# Board.net
KiCad netlist of a schematic drawn in EAGLE
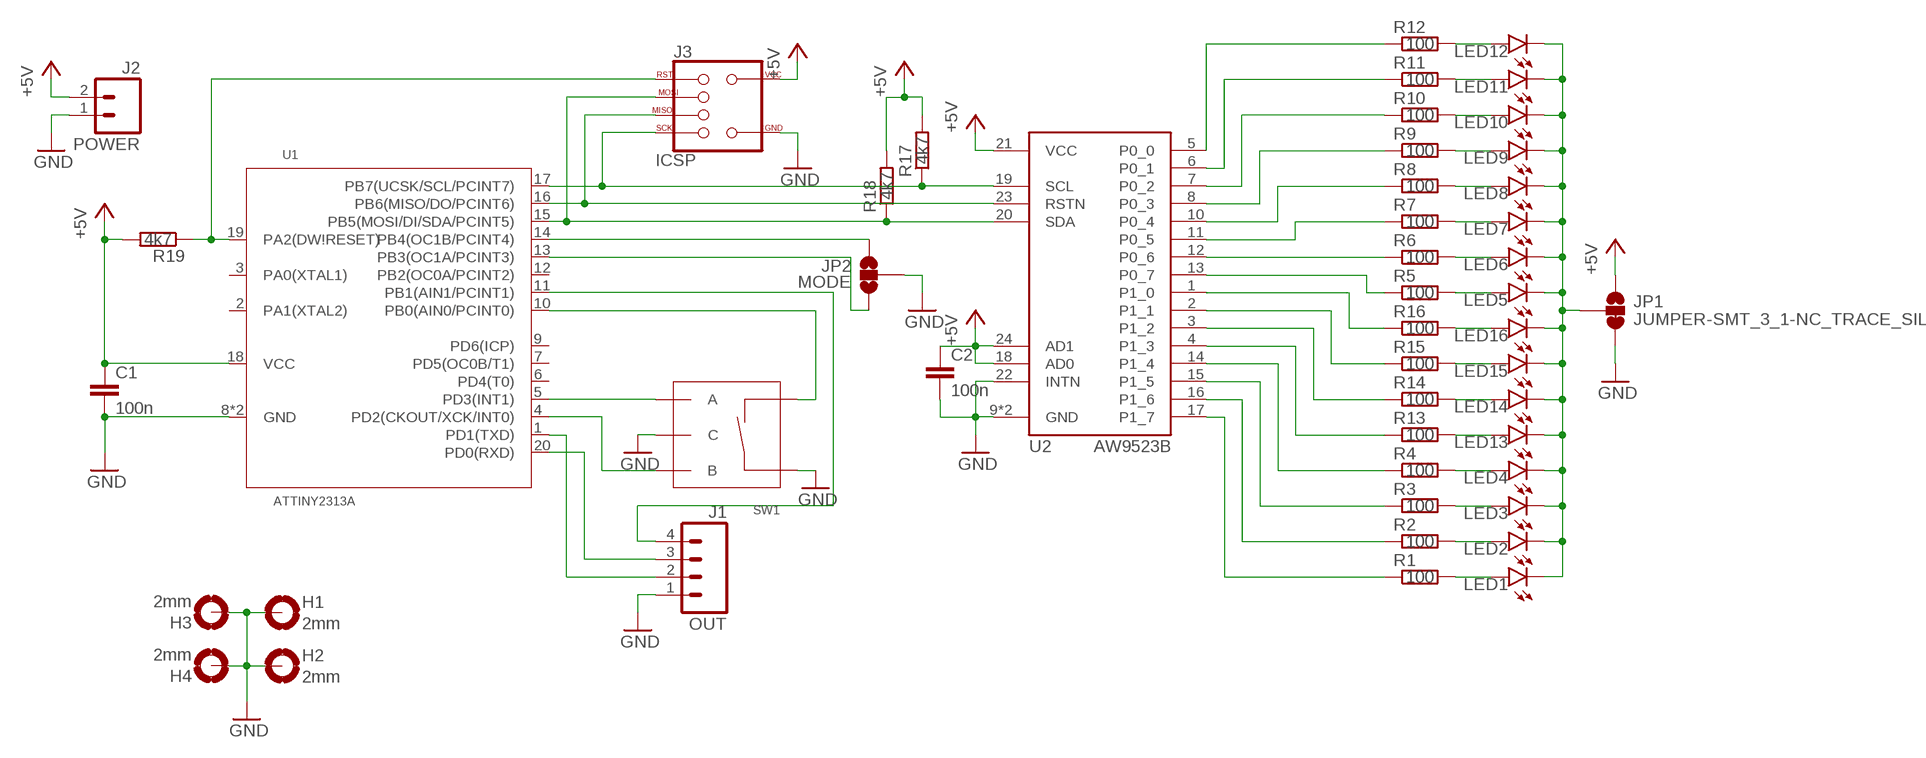
[diagram p0: schematic, sheet 1]

(export (version "E")
  (design (tool "Eeschema 10.0.6"))
  (components
    (comp (ref "C1")
      (value "100n")
      (footprint "eagle-import:C0402")
      (libsource (lib "eagle-import") (part "C-EUC0402"))
    )
    (comp (ref "C2")
      (value "100n")
      (footprint "eagle-import:C0402")
      (libsource (lib "eagle-import") (part "C-EUC0402"))
    )
    (comp (ref "H1")
      (value "2mm")
      (footprint "eagle-import:2,0-PAD")
      (libsource (lib "eagle-import") (part "MOUNT-PAD2MM"))
    )
    (comp (ref "H2")
      (value "2mm")
      (footprint "eagle-import:2,0-PAD")
      (libsource (lib "eagle-import") (part "MOUNT-PAD2MM"))
    )
    (comp (ref "H3")
      (value "2mm")
      (footprint "eagle-import:2,0-PAD")
      (libsource (lib "eagle-import") (part "MOUNT-PAD2MM"))
    )
    (comp (ref "H4")
      (value "2mm")
      (footprint "eagle-import:2,0-PAD")
      (libsource (lib "eagle-import") (part "MOUNT-PAD2MM"))
    )
    (comp (ref "J1")
      (value "OUT")
      (footprint "eagle-import:JST-4-PTH-VERT")
      (libsource (lib "eagle-import") (part "JST-XH4"))
    )
    (comp (ref "J2")
      (value "POWER")
      (footprint "eagle-import:JST-2-PTH-VERT")
      (libsource (lib "eagle-import") (part "JST-XH2"))
    )
    (comp (ref "J3")
      (value "ICSP")
      (footprint "eagle-import:MINI-ISP-LABELS")
      (libsource (lib "eagle-import") (part "MINI-ISP-LABELS"))
    )
    (comp (ref "JP1")
      (value "JUMPER-SMT_3_1-NC_TRACE_SILK")
      (footprint "eagle-import:SMT-JUMPER_3_1-NC_TRACE_SILK")
      (libsource (lib "eagle-import") (part "JUMPER-SMT_3_1-NC_TRACE_SILK"))
    )
    (comp (ref "JP2")
      (value "MODE")
      (footprint "eagle-import:SMT-JUMPER_3_NO_SILK")
      (libsource (lib "eagle-import") (part "JUMPER-SMT_3_NO_SILK"))
    )
    (comp (ref "LED1")
      (value "LED-BLUE0603")
      (footprint "eagle-import:0603-BLUE")
      (libsource (lib "eagle-import") (part "LED-BLUE0603"))
    )
    (comp (ref "LED2")
      (value "LED-BLUE0603")
      (footprint "eagle-import:0603-BLUE")
      (libsource (lib "eagle-import") (part "LED-BLUE0603"))
    )
    (comp (ref "LED3")
      (value "LED-BLUE0603")
      (footprint "eagle-import:0603-BLUE")
      (libsource (lib "eagle-import") (part "LED-BLUE0603"))
    )
    (comp (ref "LED4")
      (value "LED-BLUE0603")
      (footprint "eagle-import:0603-BLUE")
      (libsource (lib "eagle-import") (part "LED-BLUE0603"))
    )
    (comp (ref "LED5")
      (value "LED-BLUE0603")
      (footprint "eagle-import:0603-BLUE")
      (libsource (lib "eagle-import") (part "LED-BLUE0603"))
    )
    (comp (ref "LED6")
      (value "LED-BLUE0603")
      (footprint "eagle-import:0603-BLUE")
      (libsource (lib "eagle-import") (part "LED-BLUE0603"))
    )
    (comp (ref "LED7")
      (value "LED-BLUE0603")
      (footprint "eagle-import:0603-BLUE")
      (libsource (lib "eagle-import") (part "LED-BLUE0603"))
    )
    (comp (ref "LED8")
      (value "LED-BLUE0603")
      (footprint "eagle-import:0603-BLUE")
      (libsource (lib "eagle-import") (part "LED-BLUE0603"))
    )
    (comp (ref "LED9")
      (value "LED-BLUE0603")
      (footprint "eagle-import:0603-BLUE")
      (libsource (lib "eagle-import") (part "LED-BLUE0603"))
    )
    (comp (ref "LED10")
      (value "LED-BLUE0603")
      (footprint "eagle-import:0603-BLUE")
      (libsource (lib "eagle-import") (part "LED-BLUE0603"))
    )
    (comp (ref "LED11")
      (value "LED-BLUE0603")
      (footprint "eagle-import:0603-BLUE")
      (libsource (lib "eagle-import") (part "LED-BLUE0603"))
    )
    (comp (ref "LED12")
      (value "LED-BLUE0603")
      (footprint "eagle-import:0603-BLUE")
      (libsource (lib "eagle-import") (part "LED-BLUE0603"))
    )
    (comp (ref "LED13")
      (value "LED-BLUE0603")
      (footprint "eagle-import:0603-BLUE")
      (libsource (lib "eagle-import") (part "LED-BLUE0603"))
    )
    (comp (ref "LED14")
      (value "LED-BLUE0603")
      (footprint "eagle-import:0603-BLUE")
      (libsource (lib "eagle-import") (part "LED-BLUE0603"))
    )
    (comp (ref "LED15")
      (value "LED-BLUE0603")
      (footprint "eagle-import:0603-BLUE")
      (libsource (lib "eagle-import") (part "LED-BLUE0603"))
    )
    (comp (ref "LED16")
      (value "LED-BLUE0603")
      (footprint "eagle-import:0603-BLUE")
      (libsource (lib "eagle-import") (part "LED-BLUE0603"))
    )
    (comp (ref "R1")
      (value "100")
      (footprint "eagle-import:R0402")
      (libsource (lib "eagle-import") (part "R-EU_R0402"))
    )
    (comp (ref "R2")
      (value "100")
      (footprint "eagle-import:R0402")
      (libsource (lib "eagle-import") (part "R-EU_R0402"))
    )
    (comp (ref "R3")
      (value "100")
      (footprint "eagle-import:R0402")
      (libsource (lib "eagle-import") (part "R-EU_R0402"))
    )
    (comp (ref "R4")
      (value "100")
      (footprint "eagle-import:R0402")
      (libsource (lib "eagle-import") (part "R-EU_R0402"))
    )
    (comp (ref "R5")
      (value "100")
      (footprint "eagle-import:R0402")
      (libsource (lib "eagle-import") (part "R-EU_R0402"))
    )
    (comp (ref "R6")
      (value "100")
      (footprint "eagle-import:R0402")
      (libsource (lib "eagle-import") (part "R-EU_R0402"))
    )
    (comp (ref "R7")
      (value "100")
      (footprint "eagle-import:R0402")
      (libsource (lib "eagle-import") (part "R-EU_R0402"))
    )
    (comp (ref "R8")
      (value "100")
      (footprint "eagle-import:R0402")
      (libsource (lib "eagle-import") (part "R-EU_R0402"))
    )
    (comp (ref "R9")
      (value "100")
      (footprint "eagle-import:R0402")
      (libsource (lib "eagle-import") (part "R-EU_R0402"))
    )
    (comp (ref "R10")
      (value "100")
      (footprint "eagle-import:R0402")
      (libsource (lib "eagle-import") (part "R-EU_R0402"))
    )
    (comp (ref "R11")
      (value "100")
      (footprint "eagle-import:R0402")
      (libsource (lib "eagle-import") (part "R-EU_R0402"))
    )
    (comp (ref "R12")
      (value "100")
      (footprint "eagle-import:R0402")
      (libsource (lib "eagle-import") (part "R-EU_R0402"))
    )
    (comp (ref "R13")
      (value "100")
      (footprint "eagle-import:R0402")
      (libsource (lib "eagle-import") (part "R-EU_R0402"))
    )
    (comp (ref "R14")
      (value "100")
      (footprint "eagle-import:R0402")
      (libsource (lib "eagle-import") (part "R-EU_R0402"))
    )
    (comp (ref "R15")
      (value "100")
      (footprint "eagle-import:R0402")
      (libsource (lib "eagle-import") (part "R-EU_R0402"))
    )
    (comp (ref "R16")
      (value "100")
      (footprint "eagle-import:R0402")
      (libsource (lib "eagle-import") (part "R-EU_R0402"))
    )
    (comp (ref "R17")
      (value "4k7")
      (footprint "eagle-import:R0402")
      (libsource (lib "eagle-import") (part "R-EU_R0402"))
    )
    (comp (ref "R18")
      (value "4k7")
      (footprint "eagle-import:R0402")
      (libsource (lib "eagle-import") (part "R-EU_R0402"))
    )
    (comp (ref "R19")
      (value "4k7")
      (footprint "eagle-import:R0402")
      (libsource (lib "eagle-import") (part "R-EU_R0402"))
    )
    (comp (ref "SW1")
      (value "ROTARTY_ENCODER")
      (footprint "eagle-import:ROTARY_ENC_PLAIN")
      (libsource (lib "eagle-import") (part "ROTARTY_ENCODER"))
    )
    (comp (ref "U1")
      (value "ATTINY2313A")
      (footprint "eagle-import:QFN50P400X400X80-21T260N")
      (libsource (lib "eagle-import") (part "ATTINY2313A"))
    )
    (comp (ref "U2")
      (value "AW9523B")
      (footprint "eagle-import:QFN50P400X400X80-25T270N")
      (libsource (lib "eagle-import") (part "AW9523B"))
    )
  )
  (nets
    (net (code "1") (name "+5V") (class "Default")
      (node (ref "C1") (pin "1") (pinfunction "1_1") (pintype "passive"))
      (node (ref "C2") (pin "1") (pinfunction "1_1") (pintype "passive"))
      (node (ref "J2") (pin "2") (pinfunction "2_2") (pintype "passive"))
      (node (ref "J3") (pin "VDD") (pinfunction "2_VDD") (pintype "passive"))
      (node (ref "JP1") (pin "1") (pinfunction "1_1") (pintype "passive"))
      (node (ref "R17") (pin "2") (pinfunction "2_2") (pintype "passive"))
      (node (ref "R18") (pin "2") (pinfunction "2_2") (pintype "passive"))
      (node (ref "R19") (pin "2") (pinfunction "2_2") (pintype "passive"))
      (node (ref "U1") (pin "18") (pinfunction "VCC_18") (pintype "power_in"))
      (node (ref "U2") (pin "18") (pinfunction "AD0_18") (pintype "input"))
      (node (ref "U2") (pin "21") (pinfunction "VCC_21") (pintype "power_in"))
      (node (ref "U2") (pin "24") (pinfunction "AD1_24") (pintype "input"))
    )
    (net (code "2") (name "GND") (class "Default")
      (node (ref "C1") (pin "2") (pinfunction "2_2") (pintype "passive"))
      (node (ref "C2") (pin "2") (pinfunction "2_2") (pintype "passive"))
      (node (ref "H1") (pin "B2,0") (pinfunction "MOUNT_B2,0") (pintype "passive"))
      (node (ref "H2") (pin "B2,0") (pinfunction "MOUNT_B2,0") (pintype "passive"))
      (node (ref "H3") (pin "B2,0") (pinfunction "MOUNT_B2,0") (pintype "passive"))
      (node (ref "H4") (pin "B2,0") (pinfunction "MOUNT_B2,0") (pintype "passive"))
      (node (ref "J1") (pin "1") (pinfunction "1_1") (pintype "passive"))
      (node (ref "J2") (pin "1") (pinfunction "1_1") (pintype "passive"))
      (node (ref "J3") (pin "GND") (pinfunction "6_GND") (pintype "passive"))
      (node (ref "JP1") (pin "3") (pinfunction "3_3") (pintype "passive"))
      (node (ref "JP2") (pin "2") (pinfunction "2_2") (pintype "passive"))
      (node (ref "SW1") (pin "C") (pinfunction "C_C") (pintype "bidirectional"))
      (node (ref "SW1") (pin "SW+") (pinfunction "SW+_SW+") (pintype "bidirectional"))
      (node (ref "U1") (pin "21") (pinfunction "GND_21") (pintype "input"))
      (node (ref "U1") (pin "8") (pinfunction "GND_8") (pintype "input"))
      (node (ref "U2") (pin "22") (pinfunction "INTN_22") (pintype "output"))
      (node (ref "U2") (pin "25") (pinfunction "GND_25") (pintype "power_in"))
      (node (ref "U2") (pin "9") (pinfunction "GND_9") (pintype "power_in"))
    )
    (net (code "3") (name "Net-(J3-1)") (class "Default")
      (node (ref "J3") (pin "MISO") (pinfunction "1_MISO") (pintype "passive"))
      (node (ref "U1") (pin "16") (pinfunction "PB6(MISO/DO/PCINT6)_16") (pintype "input"))
      (node (ref "U2") (pin "23") (pinfunction "RSTN_23") (pintype "input"))
    )
    (net (code "4") (name "Net-(J3-3)") (class "Default")
      (node (ref "J3") (pin "SCK") (pinfunction "3_SCK") (pintype "passive"))
      (node (ref "R17") (pin "1") (pinfunction "1_1") (pintype "passive"))
      (node (ref "U1") (pin "17") (pinfunction "PB7(UCSK/SCL/PCINT7)_17") (pintype "input"))
      (node (ref "U2") (pin "19") (pinfunction "SCL_19") (pintype "input"))
    )
    (net (code "5") (name "Net-(J3-4)") (class "Default")
      (node (ref "J3") (pin "MOSI") (pinfunction "4_MOSI") (pintype "passive"))
      (node (ref "R18") (pin "1") (pinfunction "1_1") (pintype "passive"))
      (node (ref "U1") (pin "15") (pinfunction "PB5(MOSI/DI/SDA/PCINT5)_15") (pintype "output"))
      (node (ref "U2") (pin "20") (pinfunction "SDA_20") (pintype "bidirectional"))
    )
    (net (code "6") (name "Net-(J3-5)") (class "Default")
      (node (ref "J3") (pin "RESET") (pinfunction "5_RESET") (pintype "passive"))
      (node (ref "R19") (pin "1") (pinfunction "1_1") (pintype "passive"))
      (node (ref "U1") (pin "19") (pinfunction "PA2(DW\\~{RESET})_19") (pintype "output"))
    )
    (net (code "7") (name "Net-(JP1-Pad2)") (class "Default")
      (node (ref "JP1") (pin "2") (pinfunction "2_2") (pintype "passive"))
      (node (ref "LED1") (pin "C") (pinfunction "C_C") (pintype "passive"))
      (node (ref "LED10") (pin "C") (pinfunction "C_C") (pintype "passive"))
      (node (ref "LED11") (pin "C") (pinfunction "C_C") (pintype "passive"))
      (node (ref "LED12") (pin "C") (pinfunction "C_C") (pintype "passive"))
      (node (ref "LED13") (pin "C") (pinfunction "C_C") (pintype "passive"))
      (node (ref "LED14") (pin "C") (pinfunction "C_C") (pintype "passive"))
      (node (ref "LED15") (pin "C") (pinfunction "C_C") (pintype "passive"))
      (node (ref "LED16") (pin "C") (pinfunction "C_C") (pintype "passive"))
      (node (ref "LED2") (pin "C") (pinfunction "C_C") (pintype "passive"))
      (node (ref "LED3") (pin "C") (pinfunction "C_C") (pintype "passive"))
      (node (ref "LED4") (pin "C") (pinfunction "C_C") (pintype "passive"))
      (node (ref "LED5") (pin "C") (pinfunction "C_C") (pintype "passive"))
      (node (ref "LED6") (pin "C") (pinfunction "C_C") (pintype "passive"))
      (node (ref "LED7") (pin "C") (pinfunction "C_C") (pintype "passive"))
      (node (ref "LED8") (pin "C") (pinfunction "C_C") (pintype "passive"))
      (node (ref "LED9") (pin "C") (pinfunction "C_C") (pintype "passive"))
    )
    (net (code "8") (name "Net-(LED1-PadA)") (class "Default")
      (node (ref "LED1") (pin "A") (pinfunction "A_A") (pintype "passive"))
      (node (ref "R1") (pin "2") (pinfunction "2_2") (pintype "passive"))
    )
    (net (code "9") (name "Net-(LED2-PadA)") (class "Default")
      (node (ref "LED2") (pin "A") (pinfunction "A_A") (pintype "passive"))
      (node (ref "R2") (pin "2") (pinfunction "2_2") (pintype "passive"))
    )
    (net (code "10") (name "Net-(LED3-PadA)") (class "Default")
      (node (ref "LED3") (pin "A") (pinfunction "A_A") (pintype "passive"))
      (node (ref "R3") (pin "2") (pinfunction "2_2") (pintype "passive"))
    )
    (net (code "11") (name "Net-(LED4-PadA)") (class "Default")
      (node (ref "LED4") (pin "A") (pinfunction "A_A") (pintype "passive"))
      (node (ref "R4") (pin "2") (pinfunction "2_2") (pintype "passive"))
    )
    (net (code "12") (name "Net-(LED5-PadA)") (class "Default")
      (node (ref "LED5") (pin "A") (pinfunction "A_A") (pintype "passive"))
      (node (ref "R5") (pin "2") (pinfunction "2_2") (pintype "passive"))
    )
    (net (code "13") (name "Net-(LED6-PadA)") (class "Default")
      (node (ref "LED6") (pin "A") (pinfunction "A_A") (pintype "passive"))
      (node (ref "R6") (pin "2") (pinfunction "2_2") (pintype "passive"))
    )
    (net (code "14") (name "Net-(LED7-PadA)") (class "Default")
      (node (ref "LED7") (pin "A") (pinfunction "A_A") (pintype "passive"))
      (node (ref "R7") (pin "2") (pinfunction "2_2") (pintype "passive"))
    )
    (net (code "15") (name "Net-(LED8-PadA)") (class "Default")
      (node (ref "LED8") (pin "A") (pinfunction "A_A") (pintype "passive"))
      (node (ref "R8") (pin "2") (pinfunction "2_2") (pintype "passive"))
    )
    (net (code "16") (name "Net-(LED9-PadA)") (class "Default")
      (node (ref "LED9") (pin "A") (pinfunction "A_A") (pintype "passive"))
      (node (ref "R9") (pin "2") (pinfunction "2_2") (pintype "passive"))
    )
    (net (code "17") (name "Net-(LED10-PadA)") (class "Default")
      (node (ref "LED10") (pin "A") (pinfunction "A_A") (pintype "passive"))
      (node (ref "R10") (pin "2") (pinfunction "2_2") (pintype "passive"))
    )
    (net (code "18") (name "Net-(LED11-PadA)") (class "Default")
      (node (ref "LED11") (pin "A") (pinfunction "A_A") (pintype "passive"))
      (node (ref "R11") (pin "2") (pinfunction "2_2") (pintype "passive"))
    )
    (net (code "19") (name "Net-(LED12-PadA)") (class "Default")
      (node (ref "LED12") (pin "A") (pinfunction "A_A") (pintype "passive"))
      (node (ref "R12") (pin "2") (pinfunction "2_2") (pintype "passive"))
    )
    (net (code "20") (name "Net-(LED13-PadA)") (class "Default")
      (node (ref "LED13") (pin "A") (pinfunction "A_A") (pintype "passive"))
      (node (ref "R13") (pin "2") (pinfunction "2_2") (pintype "passive"))
    )
    (net (code "21") (name "Net-(LED14-PadA)") (class "Default")
      (node (ref "LED14") (pin "A") (pinfunction "A_A") (pintype "passive"))
      (node (ref "R14") (pin "2") (pinfunction "2_2") (pintype "passive"))
    )
    (net (code "22") (name "Net-(LED15-PadA)") (class "Default")
      (node (ref "LED15") (pin "A") (pinfunction "A_A") (pintype "passive"))
      (node (ref "R15") (pin "2") (pinfunction "2_2") (pintype "passive"))
    )
    (net (code "23") (name "Net-(LED16-PadA)") (class "Default")
      (node (ref "LED16") (pin "A") (pinfunction "A_A") (pintype "passive"))
      (node (ref "R16") (pin "2") (pinfunction "2_2") (pintype "passive"))
    )
    (net (code "24") (name "Net-(U1-PB0(AIN0{slash}PCINT0))") (class "Default")
      (node (ref "SW1") (pin "SW-") (pinfunction "SW-_SW-") (pintype "bidirectional"))
      (node (ref "U1") (pin "10") (pinfunction "PB0(AIN0/PCINT0)_10") (pintype "output"))
    )
    (net (code "25") (name "Net-(U1-PB1(AIN1{slash}PCINT1))") (class "Default")
      (node (ref "J1") (pin "4") (pinfunction "4_4") (pintype "passive"))
      (node (ref "U1") (pin "11") (pinfunction "PB1(AIN1/PCINT1)_11") (pintype "output"))
    )
    (net (code "26") (name "Net-(U1-PB3(OC1A{slash}PCINT3))") (class "Default")
      (node (ref "JP2") (pin "3") (pinfunction "3_3") (pintype "passive"))
      (node (ref "U1") (pin "13") (pinfunction "PB3(OC1A/PCINT3)_13") (pintype "input"))
    )
    (net (code "27") (name "Net-(U1-PB4(OC1B{slash}PCINT4))") (class "Default")
      (node (ref "JP2") (pin "1") (pinfunction "1_1") (pintype "passive"))
      (node (ref "U1") (pin "14") (pinfunction "PB4(OC1B/PCINT4)_14") (pintype "input"))
    )
    (net (code "28") (name "Net-(U1-PD0(RXD))") (class "Default")
      (node (ref "J1") (pin "3") (pinfunction "3_3") (pintype "passive"))
      (node (ref "U1") (pin "20") (pinfunction "PD0(RXD)_20") (pintype "input"))
    )
    (net (code "29") (name "Net-(U1-PD1(TXD))") (class "Default")
      (node (ref "J1") (pin "2") (pinfunction "2_2") (pintype "passive"))
      (node (ref "U1") (pin "1") (pinfunction "PD1(TXD)_1") (pintype "output"))
    )
    (net (code "30") (name "Net-(U1-PD2(CKOUT{slash}XCK{slash}INT0))") (class "Default")
      (node (ref "SW1") (pin "B") (pinfunction "B_B") (pintype "bidirectional"))
      (node (ref "U1") (pin "4") (pinfunction "PD2(CKOUT/XCK/INT0)_4") (pintype "input"))
    )
    (net (code "31") (name "Net-(U1-PD3(INT1))") (class "Default")
      (node (ref "SW1") (pin "A") (pinfunction "A_A") (pintype "bidirectional"))
      (node (ref "U1") (pin "5") (pinfunction "PD3(INT1)_5") (pintype "output"))
    )
    (net (code "32") (name "Net-(U2-P0_0)") (class "Default")
      (node (ref "R12") (pin "1") (pinfunction "1_1") (pintype "passive"))
      (node (ref "U2") (pin "5") (pinfunction "P0_0_5") (pintype "bidirectional"))
    )
    (net (code "33") (name "Net-(U2-P0_1)") (class "Default")
      (node (ref "R11") (pin "1") (pinfunction "1_1") (pintype "passive"))
      (node (ref "U2") (pin "6") (pinfunction "P0_1_6") (pintype "bidirectional"))
    )
    (net (code "34") (name "Net-(U2-P0_2)") (class "Default")
      (node (ref "R10") (pin "1") (pinfunction "1_1") (pintype "passive"))
      (node (ref "U2") (pin "7") (pinfunction "P0_2_7") (pintype "bidirectional"))
    )
    (net (code "35") (name "Net-(U2-P0_3)") (class "Default")
      (node (ref "R9") (pin "1") (pinfunction "1_1") (pintype "passive"))
      (node (ref "U2") (pin "8") (pinfunction "P0_3_8") (pintype "bidirectional"))
    )
    (net (code "36") (name "Net-(U2-P0_4)") (class "Default")
      (node (ref "R8") (pin "1") (pinfunction "1_1") (pintype "passive"))
      (node (ref "U2") (pin "10") (pinfunction "P0_4_10") (pintype "bidirectional"))
    )
    (net (code "37") (name "Net-(U2-P0_5)") (class "Default")
      (node (ref "R7") (pin "1") (pinfunction "1_1") (pintype "passive"))
      (node (ref "U2") (pin "11") (pinfunction "P0_5_11") (pintype "bidirectional"))
    )
    (net (code "38") (name "Net-(U2-P0_6)") (class "Default")
      (node (ref "R6") (pin "1") (pinfunction "1_1") (pintype "passive"))
      (node (ref "U2") (pin "12") (pinfunction "P0_6_12") (pintype "bidirectional"))
    )
    (net (code "39") (name "Net-(U2-P0_7)") (class "Default")
      (node (ref "R5") (pin "1") (pinfunction "1_1") (pintype "passive"))
      (node (ref "U2") (pin "13") (pinfunction "P0_7_13") (pintype "bidirectional"))
    )
    (net (code "40") (name "Net-(U2-P1_0)") (class "Default")
      (node (ref "R16") (pin "1") (pinfunction "1_1") (pintype "passive"))
      (node (ref "U2") (pin "1") (pinfunction "P1_0_1") (pintype "bidirectional"))
    )
    (net (code "41") (name "Net-(U2-P1_1)") (class "Default")
      (node (ref "R15") (pin "1") (pinfunction "1_1") (pintype "passive"))
      (node (ref "U2") (pin "2") (pinfunction "P1_1_2") (pintype "bidirectional"))
    )
    (net (code "42") (name "Net-(U2-P1_2)") (class "Default")
      (node (ref "R14") (pin "1") (pinfunction "1_1") (pintype "passive"))
      (node (ref "U2") (pin "3") (pinfunction "P1_2_3") (pintype "bidirectional"))
    )
    (net (code "43") (name "Net-(U2-P1_3)") (class "Default")
      (node (ref "R13") (pin "1") (pinfunction "1_1") (pintype "passive"))
      (node (ref "U2") (pin "4") (pinfunction "P1_3_4") (pintype "bidirectional"))
    )
    (net (code "44") (name "Net-(U2-P1_4)") (class "Default")
      (node (ref "R4") (pin "1") (pinfunction "1_1") (pintype "passive"))
      (node (ref "U2") (pin "14") (pinfunction "P1_4_14") (pintype "bidirectional"))
    )
    (net (code "45") (name "Net-(U2-P1_5)") (class "Default")
      (node (ref "R3") (pin "1") (pinfunction "1_1") (pintype "passive"))
      (node (ref "U2") (pin "15") (pinfunction "P1_5_15") (pintype "bidirectional"))
    )
    (net (code "46") (name "Net-(U2-P1_6)") (class "Default")
      (node (ref "R2") (pin "1") (pinfunction "1_1") (pintype "passive"))
      (node (ref "U2") (pin "16") (pinfunction "P1_6_16") (pintype "bidirectional"))
    )
    (net (code "47") (name "Net-(U2-P1_7)") (class "Default")
      (node (ref "R1") (pin "1") (pinfunction "1_1") (pintype "passive"))
      (node (ref "U2") (pin "17") (pinfunction "P1_7_17") (pintype "bidirectional"))
    )
    (net (code "48") (name "unconnected-(U1-PA0(XTAL1)-Pad3)") (class "Default")
      (node (ref "U1") (pin "3") (pinfunction "PA0(XTAL1)_3") (pintype "input"))
    )
    (net (code "49") (name "unconnected-(U1-PA1(XTAL2)-Pad2)") (class "Default")
      (node (ref "U1") (pin "2") (pinfunction "PA1(XTAL2)_2") (pintype "input"))
    )
    (net (code "50") (name "unconnected-(U1-PB2(OC0A{slash}PCINT2)-Pad12)") (class "Default")
      (node (ref "U1") (pin "12") (pinfunction "PB2(OC0A/PCINT2)_12") (pintype "output"))
    )
    (net (code "51") (name "unconnected-(U1-PD4(T0)-Pad6)") (class "Default")
      (node (ref "U1") (pin "6") (pinfunction "PD4(T0)_6") (pintype "input"))
    )
    (net (code "52") (name "unconnected-(U1-PD5(OC0B{slash}T1)-Pad7)") (class "Default")
      (node (ref "U1") (pin "7") (pinfunction "PD5(OC0B/T1)_7") (pintype "input"))
    )
    (net (code "53") (name "unconnected-(U1-PD6(ICP)-Pad9)") (class "Default")
      (node (ref "U1") (pin "9") (pinfunction "PD6(ICP)_9") (pintype "output"))
    )
  )
)
